# v1_1_0.net
KiCad netlist of a schematic drawn in EAGLE
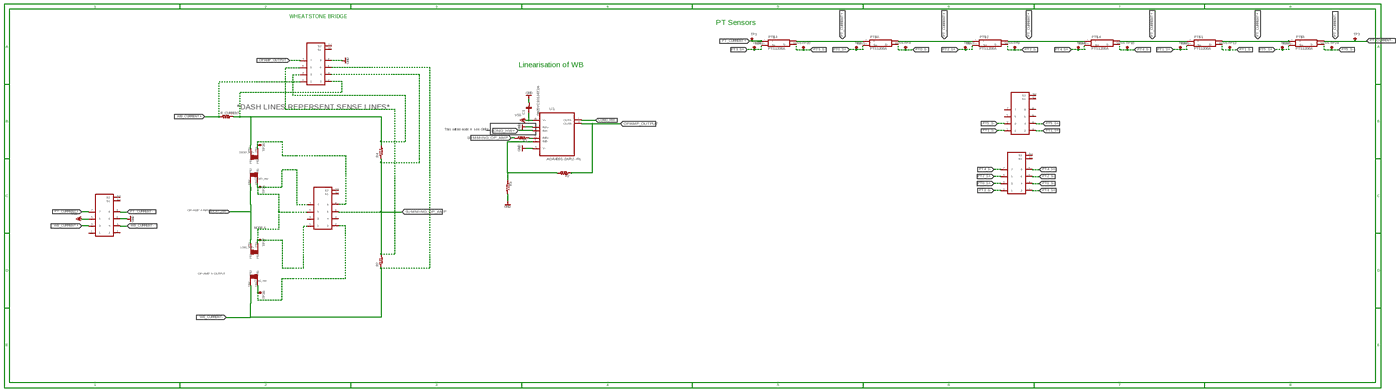
[diagram p0: schematic, sheet 1, overview]
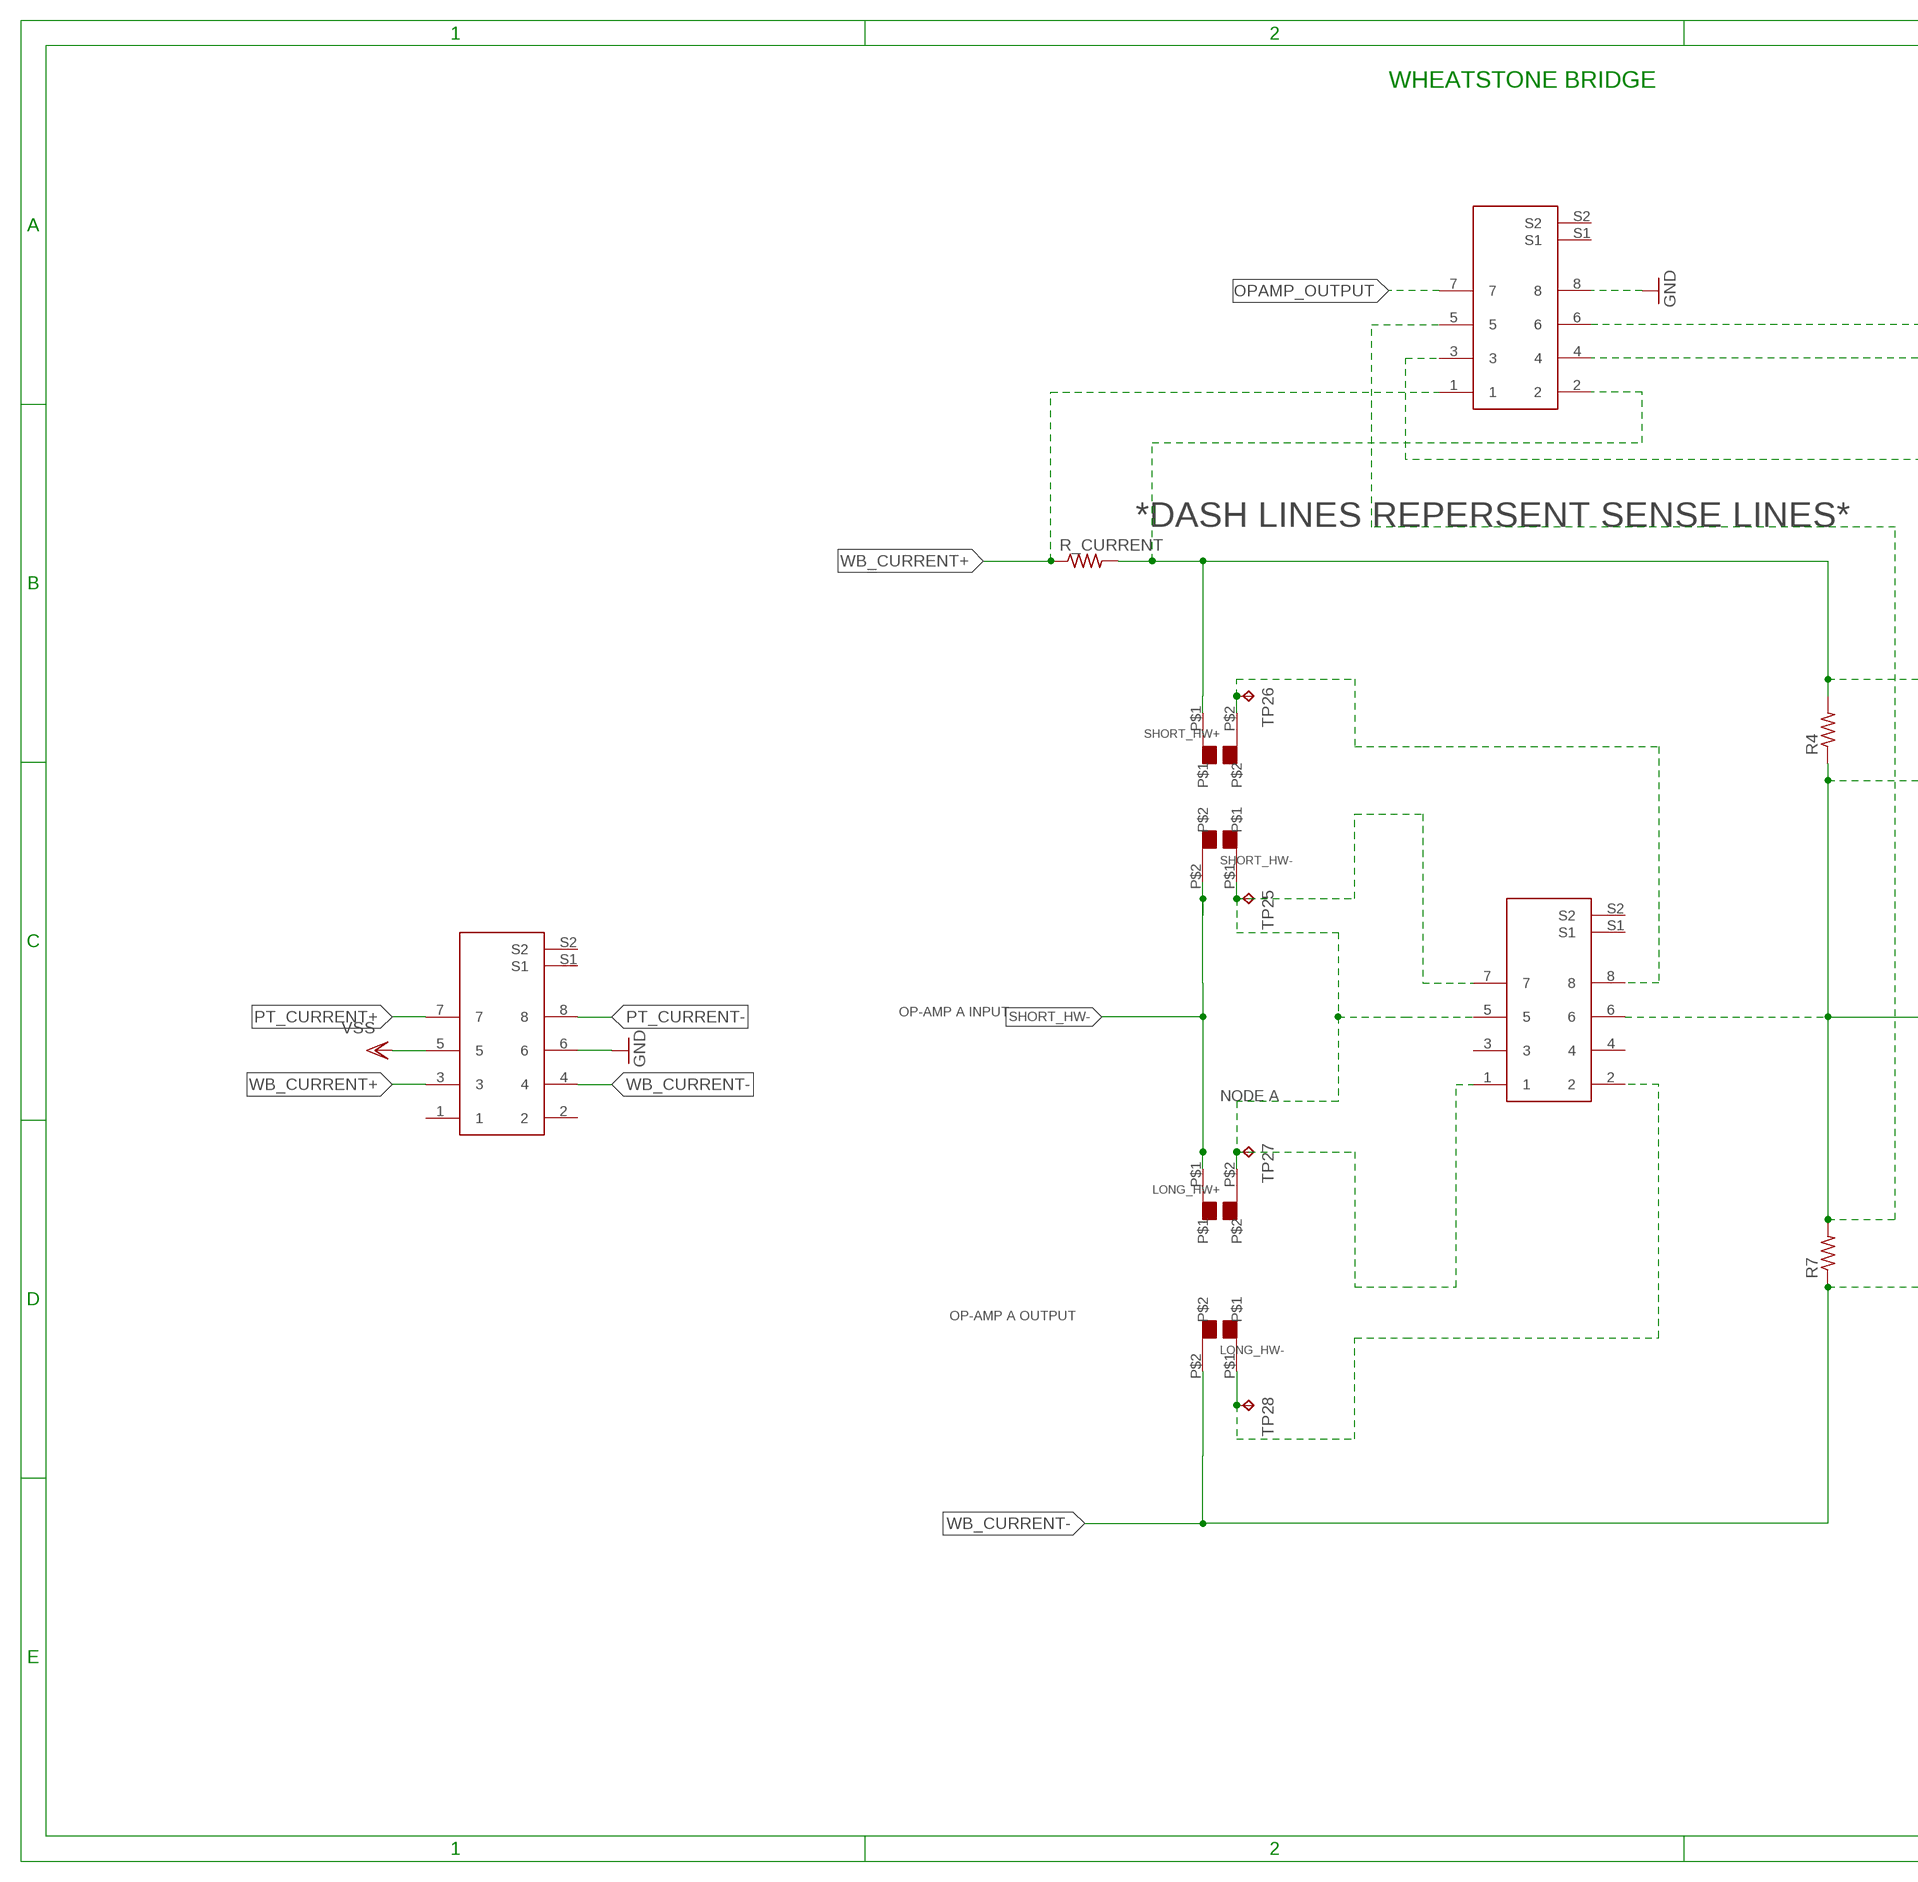
[diagram p1: schematic, sheet 1, part 1 of 4]
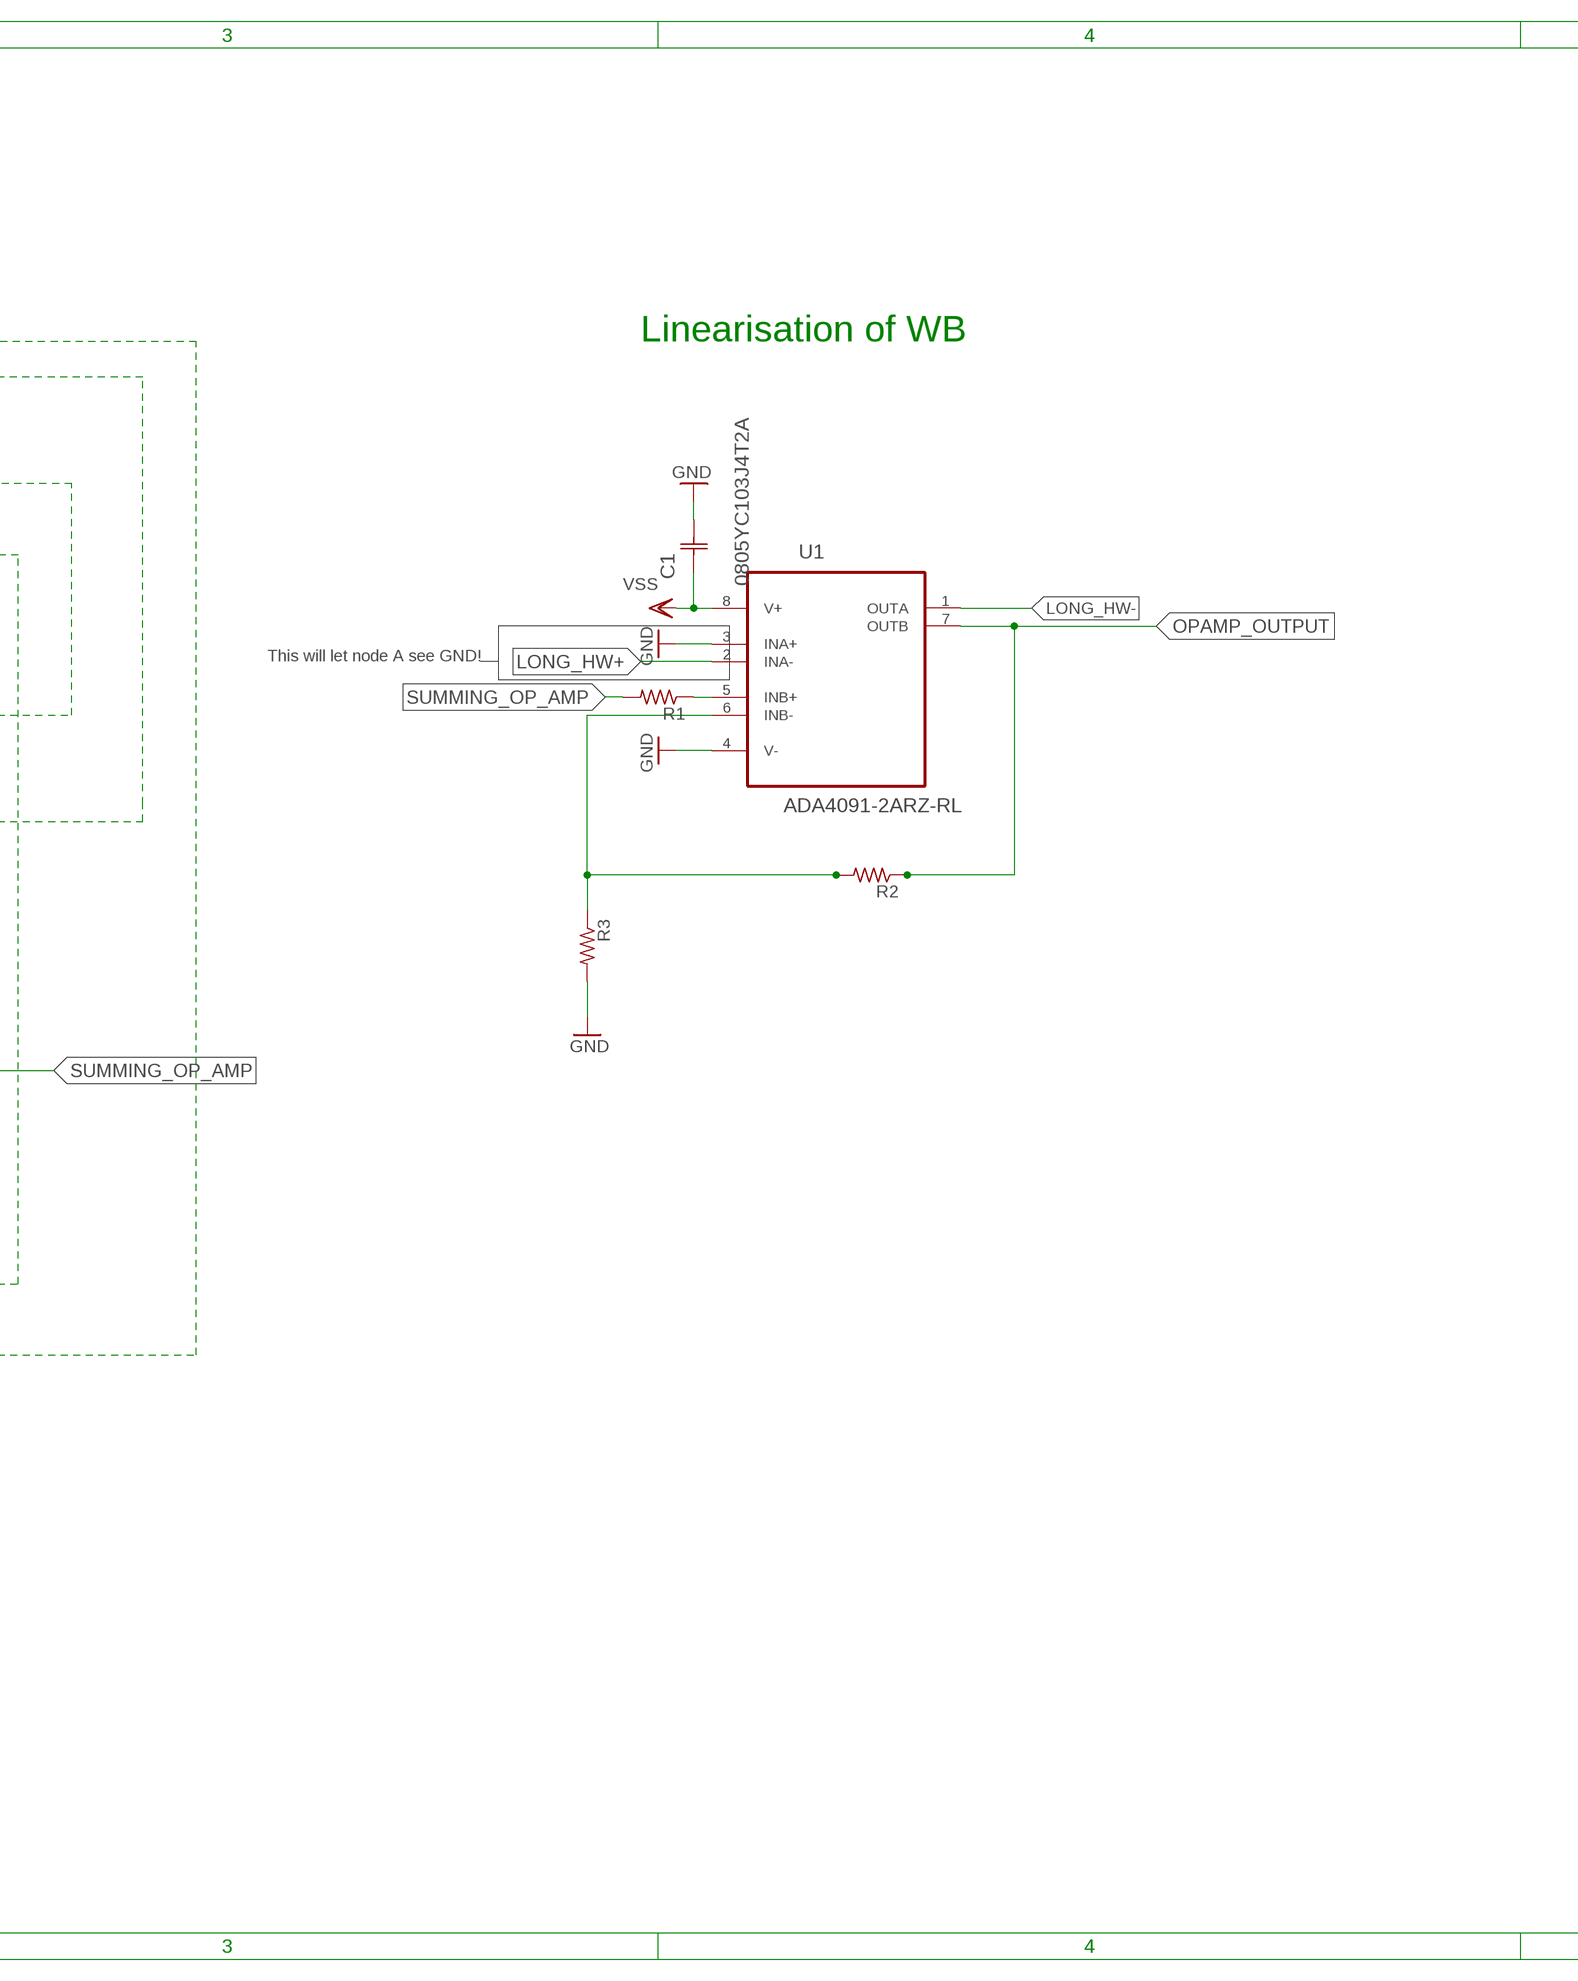
[diagram p2: schematic, sheet 1, part 2 of 4]
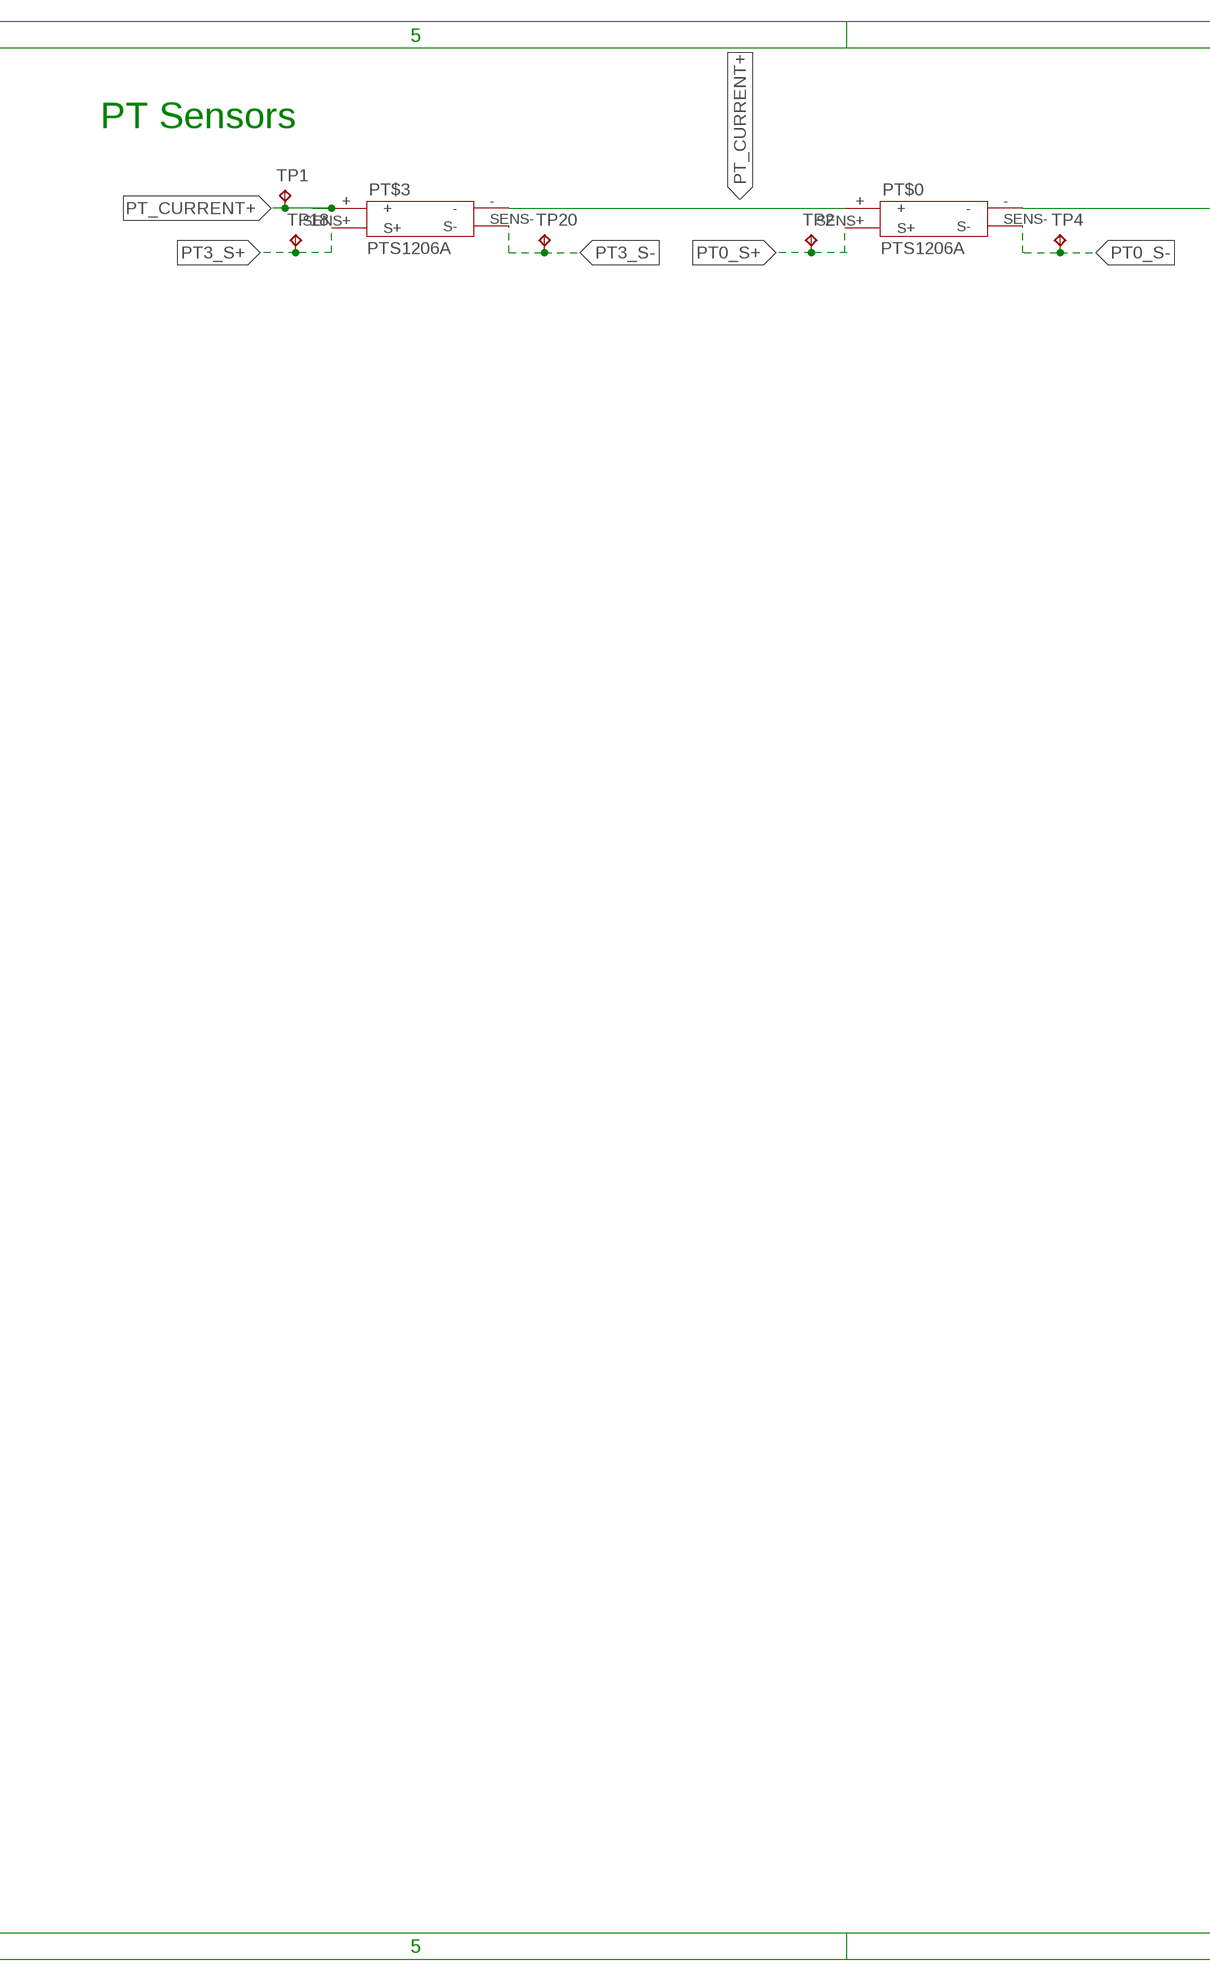
[diagram p3: schematic, sheet 1, part 3 of 4]
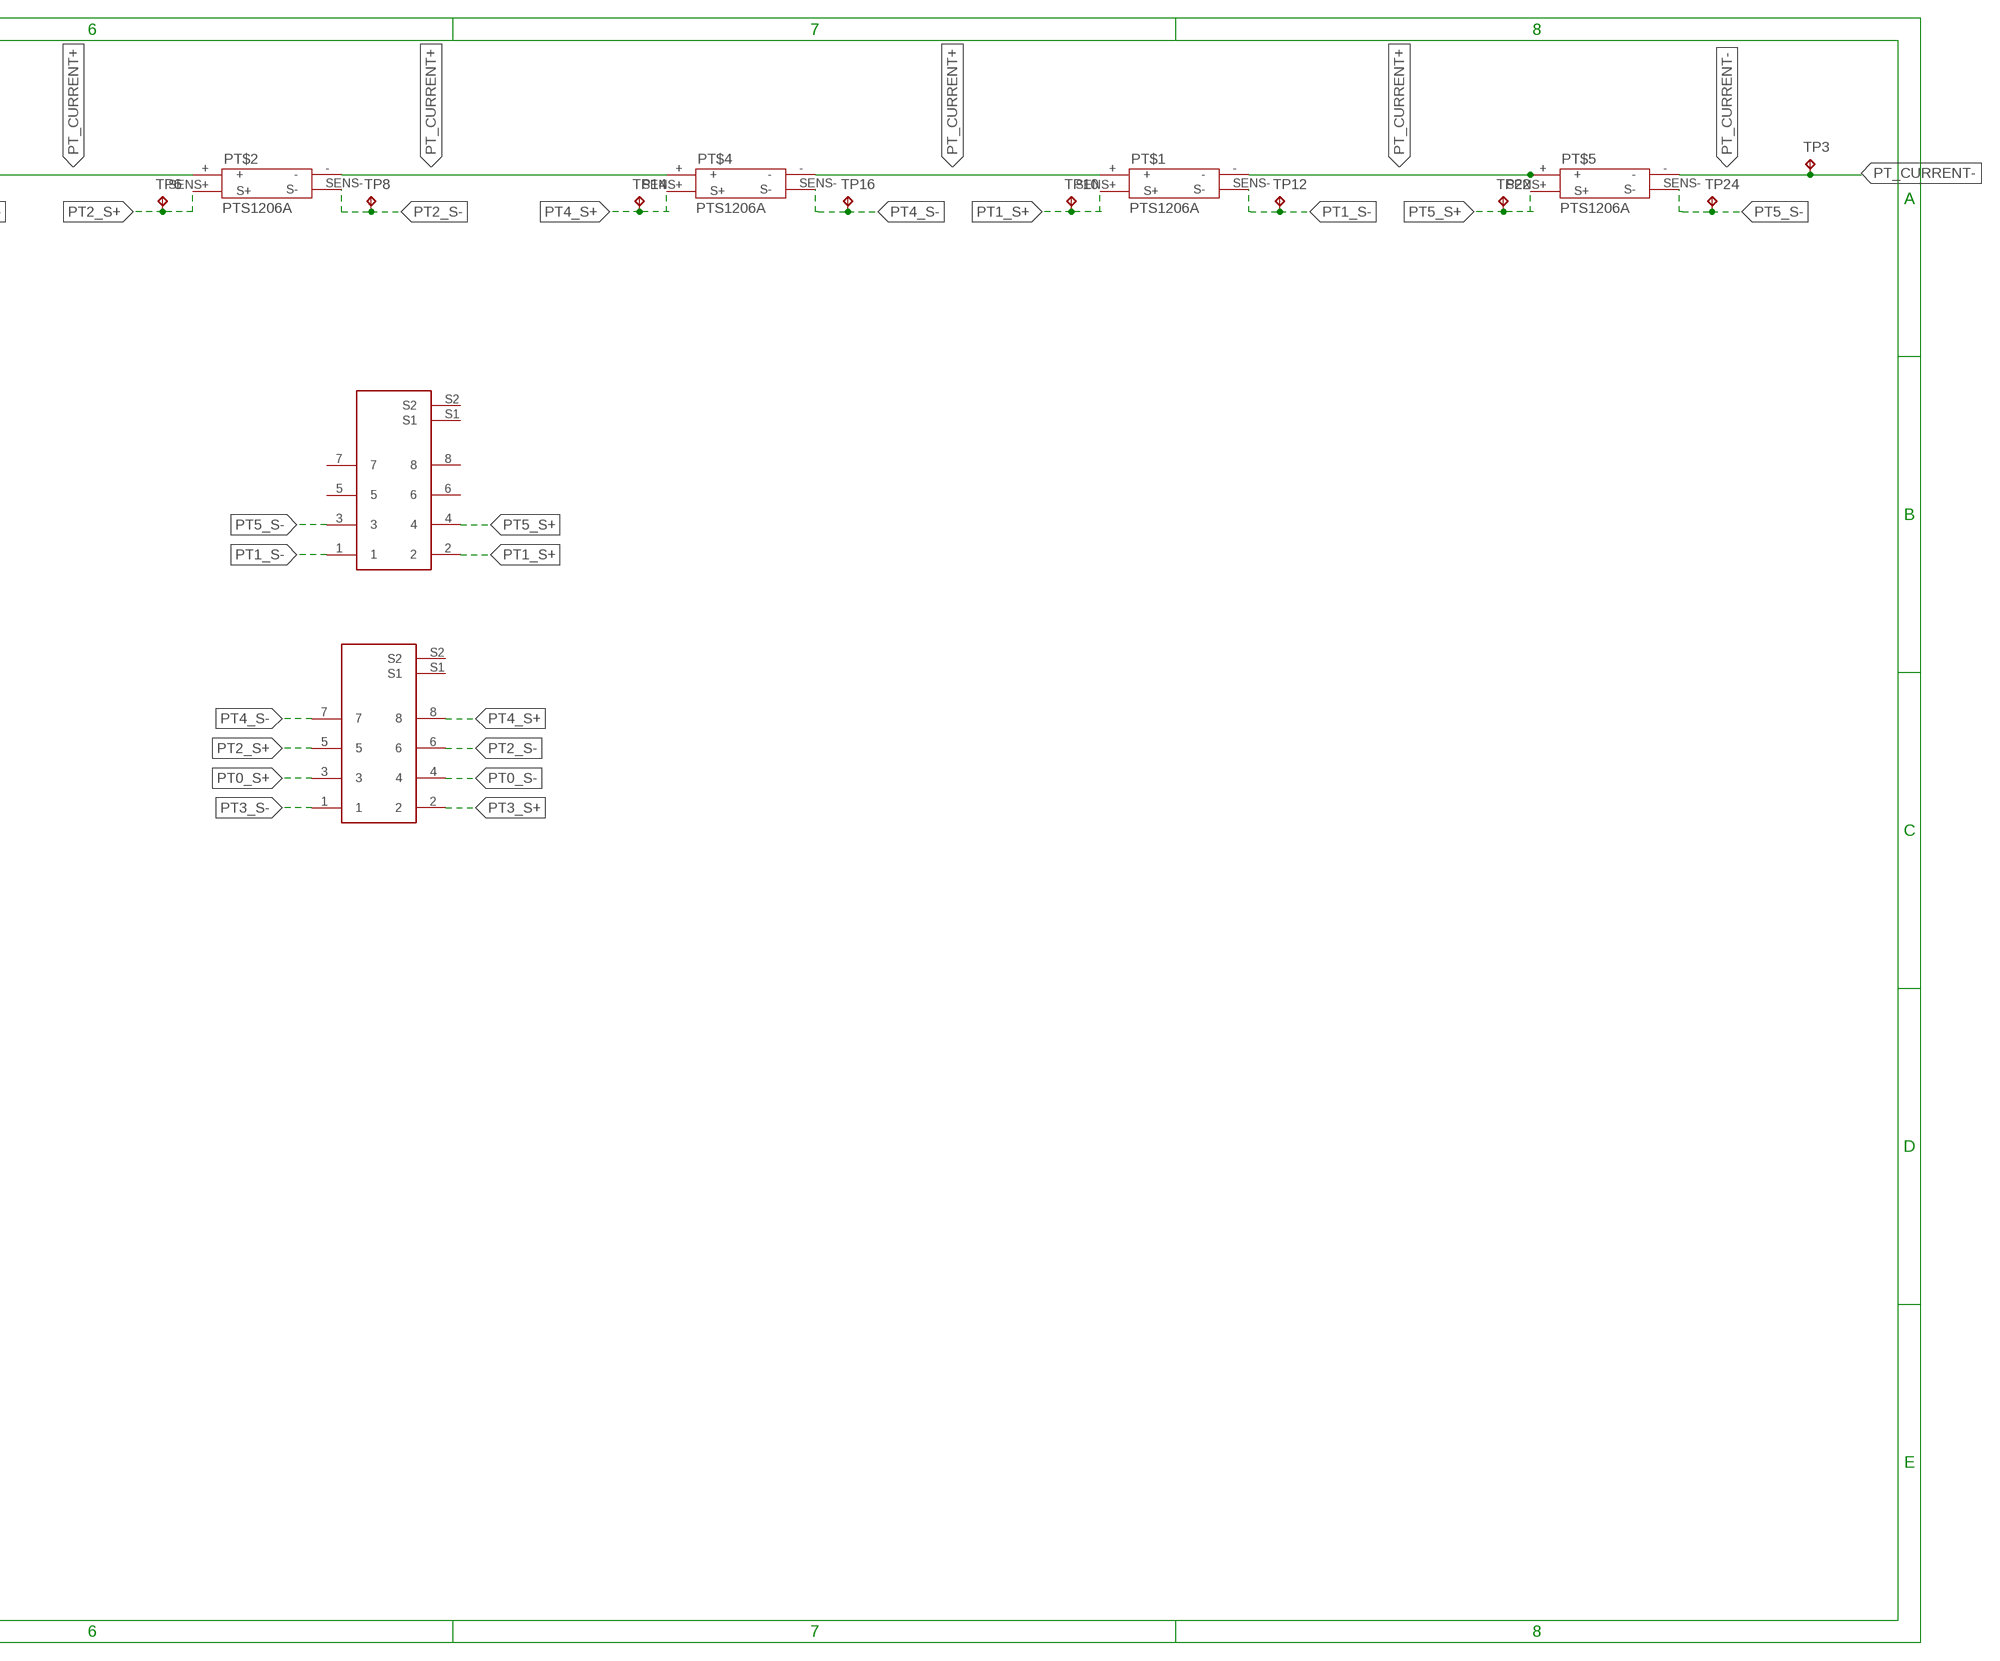
[diagram p4: schematic, sheet 1, part 4 of 4]

(export (version "E")
  (design (tool "Eeschema 10.0.6"))
  (components
    (comp (ref "C1")
      (value "0805YC103J4T2A")
      (footprint "eagle-import:CAPC2012X94N")
      (fields (field (name "MF") "AVX"))
      (libsource (lib "eagle-import") (part "0805YC103J4T2A"))
    )
    (comp (ref "LONG_HW+")
      (value "WIREPOINT_1A")
      (footprint "eagle-import:WIREPOINT")
      (libsource (lib "eagle-import") (part "WIREPOINT_1A"))
    )
    (comp (ref "LONG_HW-")
      (value "WIREPOINT_1A")
      (footprint "eagle-import:WIREPOINT")
      (libsource (lib "eagle-import") (part "WIREPOINT_1A"))
    )
    (comp (ref "POWER")
      (value "RJ45_CONNECTOR")
      (footprint "eagle-import:RJ45_CONNNECTOR")
      (libsource (lib "eagle-import") (part "RJ45_CONNECTOR"))
    )
    (comp (ref "PT$0")
      (value "PTS1206A")
      (footprint "eagle-import:CAPMP3216X166")
      (libsource (lib "eagle-import") (part "PTS1206A"))
    )
    (comp (ref "PT$1")
      (value "PTS1206A")
      (footprint "eagle-import:CAPMP3216X166")
      (libsource (lib "eagle-import") (part "PTS1206A"))
    )
    (comp (ref "PT$2")
      (value "PTS1206A")
      (footprint "eagle-import:CAPMP3216X166")
      (libsource (lib "eagle-import") (part "PTS1206A"))
    )
    (comp (ref "PT$3")
      (value "PTS1206A")
      (footprint "eagle-import:CAPMP3216X166")
      (libsource (lib "eagle-import") (part "PTS1206A"))
    )
    (comp (ref "PT$4")
      (value "PTS1206A")
      (footprint "eagle-import:CAPMP3216X166")
      (libsource (lib "eagle-import") (part "PTS1206A"))
    )
    (comp (ref "PT$5")
      (value "PTS1206A")
      (footprint "eagle-import:CAPMP3216X166")
      (libsource (lib "eagle-import") (part "PTS1206A"))
    )
    (comp (ref "PT_SENS1")
      (value "RJ45_CONNECTOR")
      (footprint "eagle-import:RJ45_CONNNECTOR")
      (libsource (lib "eagle-import") (part "RJ45_CONNECTOR"))
    )
    (comp (ref "PT_SENS2")
      (value "RJ45_CONNECTOR")
      (footprint "eagle-import:RJ45_CONNNECTOR")
      (libsource (lib "eagle-import") (part "RJ45_CONNECTOR"))
    )
    (comp (ref "R1")
      (value "R-US_M0805")
      (footprint "eagle-import:M0805")
      (libsource (lib "eagle-import") (part "R-US_M0805"))
    )
    (comp (ref "R2")
      (value "R-US_M0805")
      (footprint "eagle-import:M0805")
      (libsource (lib "eagle-import") (part "R-US_M0805"))
    )
    (comp (ref "R3")
      (value "R-US_M0805")
      (footprint "eagle-import:M0805")
      (libsource (lib "eagle-import") (part "R-US_M0805"))
    )
    (comp (ref "R4")
      (value "R-US_M0805")
      (footprint "eagle-import:M0805")
      (libsource (lib "eagle-import") (part "R-US_M0805"))
    )
    (comp (ref "R7")
      (value "R-US_M0805")
      (footprint "eagle-import:M0805")
      (libsource (lib "eagle-import") (part "R-US_M0805"))
    )
    (comp (ref "R_CURRENT")
      (value "R-US_M0805")
      (footprint "eagle-import:M0805")
      (libsource (lib "eagle-import") (part "R-US_M0805"))
    )
    (comp (ref "SHORT_HW+")
      (value "WIREPOINT_1A")
      (footprint "eagle-import:WIREPOINT")
      (libsource (lib "eagle-import") (part "WIREPOINT_1A"))
    )
    (comp (ref "SHORT_HW-")
      (value "WIREPOINT_1A")
      (footprint "eagle-import:WIREPOINT")
      (libsource (lib "eagle-import") (part "WIREPOINT_1A"))
    )
    (comp (ref "TP1")
      (value "TPTP10SQ")
      (footprint "eagle-import:TP10SQ")
      (libsource (lib "eagle-import") (part "TPTP10SQ"))
    )
    (comp (ref "TP2")
      (value "TPTP10SQ")
      (footprint "eagle-import:TP10SQ")
      (libsource (lib "eagle-import") (part "TPTP10SQ"))
    )
    (comp (ref "TP3")
      (value "TPTP10SQ")
      (footprint "eagle-import:TP10SQ")
      (libsource (lib "eagle-import") (part "TPTP10SQ"))
    )
    (comp (ref "TP4")
      (value "TPTP10SQ")
      (footprint "eagle-import:TP10SQ")
      (libsource (lib "eagle-import") (part "TPTP10SQ"))
    )
    (comp (ref "TP6")
      (value "TPTP10SQ")
      (footprint "eagle-import:TP10SQ")
      (libsource (lib "eagle-import") (part "TPTP10SQ"))
    )
    (comp (ref "TP8")
      (value "TPTP10SQ")
      (footprint "eagle-import:TP10SQ")
      (libsource (lib "eagle-import") (part "TPTP10SQ"))
    )
    (comp (ref "TP10")
      (value "TPTP10SQ")
      (footprint "eagle-import:TP10SQ")
      (libsource (lib "eagle-import") (part "TPTP10SQ"))
    )
    (comp (ref "TP12")
      (value "TPTP10SQ")
      (footprint "eagle-import:TP10SQ")
      (libsource (lib "eagle-import") (part "TPTP10SQ"))
    )
    (comp (ref "TP14")
      (value "TPTP10SQ")
      (footprint "eagle-import:TP10SQ")
      (libsource (lib "eagle-import") (part "TPTP10SQ"))
    )
    (comp (ref "TP16")
      (value "TPTP10SQ")
      (footprint "eagle-import:TP10SQ")
      (libsource (lib "eagle-import") (part "TPTP10SQ"))
    )
    (comp (ref "TP18")
      (value "TPTP10SQ")
      (footprint "eagle-import:TP10SQ")
      (libsource (lib "eagle-import") (part "TPTP10SQ"))
    )
    (comp (ref "TP20")
      (value "TPTP10SQ")
      (footprint "eagle-import:TP10SQ")
      (libsource (lib "eagle-import") (part "TPTP10SQ"))
    )
    (comp (ref "TP22")
      (value "TPTP10SQ")
      (footprint "eagle-import:TP10SQ")
      (libsource (lib "eagle-import") (part "TPTP10SQ"))
    )
    (comp (ref "TP24")
      (value "TPTP10SQ")
      (footprint "eagle-import:TP10SQ")
      (libsource (lib "eagle-import") (part "TPTP10SQ"))
    )
    (comp (ref "TP25")
      (value "TPTP10SQ")
      (footprint "eagle-import:TP10SQ")
      (libsource (lib "eagle-import") (part "TPTP10SQ"))
    )
    (comp (ref "TP26")
      (value "TPTP10SQ")
      (footprint "eagle-import:TP10SQ")
      (libsource (lib "eagle-import") (part "TPTP10SQ"))
    )
    (comp (ref "TP27")
      (value "TPTP10SQ")
      (footprint "eagle-import:TP10SQ")
      (libsource (lib "eagle-import") (part "TPTP10SQ"))
    )
    (comp (ref "TP28")
      (value "TPTP10SQ")
      (footprint "eagle-import:TP10SQ")
      (libsource (lib "eagle-import") (part "TPTP10SQ"))
    )
    (comp (ref "U1")
      (value "ADA4091-2ARZ-RL")
      (footprint "eagle-import:SOIC127P600X175-8N")
      (fields (field (name "MF") "Analog"))
      (libsource (lib "eagle-import") (part "ADA4091-2ARZ-RL"))
    )
    (comp (ref "WB_SENS1")
      (value "RJ45_CONNECTOR")
      (footprint "eagle-import:RJ45_CONNNECTOR")
      (libsource (lib "eagle-import") (part "RJ45_CONNECTOR"))
    )
    (comp (ref "WB_SENS2")
      (value "RJ45_CONNECTOR")
      (footprint "eagle-import:RJ45_CONNNECTOR")
      (libsource (lib "eagle-import") (part "RJ45_CONNECTOR"))
    )
  )
  (nets
    (net (code "1") (name "GND") (class "Default")
      (node (ref "C1") (pin "2") (pinfunction "C2_2") (pintype "passive"))
      (node (ref "POWER") (pin "6") (pinfunction "6_6") (pintype "bidirectional"))
      (node (ref "R3") (pin "2") (pinfunction "2_2") (pintype "passive"))
      (node (ref "U1") (pin "3") (pinfunction "INA+_3") (pintype "input"))
      (node (ref "U1") (pin "4") (pinfunction "V-_4") (pintype "power_in"))
      (node (ref "WB_SENS2") (pin "8") (pinfunction "8_8") (pintype "bidirectional"))
    )
    (net (code "2") (name "LONG_HW+") (class "Default")
      (node (ref "U1") (pin "2") (pinfunction "INA-_2") (pintype "input"))
    )
    (net (code "3") (name "LONG_HW-") (class "Default")
      (node (ref "U1") (pin "1") (pinfunction "OUTA_1") (pintype "output"))
    )
    (net (code "4") (name "Net-(LONG_HW+-PadP$2)") (class "Default")
      (node (ref "LONG_HW+") (pin "P$2") (pinfunction "P$2_P$2") (pintype "bidirectional"))
      (node (ref "SHORT_HW-") (pin "P$1") (pinfunction "P$1_P$1") (pintype "bidirectional"))
      (node (ref "TP25") (pin "TP") (pinfunction "TP_TP") (pintype "input"))
      (node (ref "TP27") (pin "TP") (pinfunction "TP_TP") (pintype "input"))
      (node (ref "WB_SENS1") (pin "1") (pinfunction "1_1") (pintype "bidirectional"))
      (node (ref "WB_SENS1") (pin "5") (pinfunction "5_5") (pintype "bidirectional"))
      (node (ref "WB_SENS1") (pin "7") (pinfunction "7_7") (pintype "bidirectional"))
    )
    (net (code "5") (name "Net-(LONG_HW--PadP$1)") (class "Default")
      (node (ref "LONG_HW-") (pin "P$1") (pinfunction "P$1_P$1") (pintype "bidirectional"))
      (node (ref "TP28") (pin "TP") (pinfunction "TP_TP") (pintype "input"))
      (node (ref "WB_SENS1") (pin "2") (pinfunction "2_2") (pintype "bidirectional"))
    )
    (net (code "6") (name "Net-(SHORT_HW+-PadP$2)") (class "Default")
      (node (ref "SHORT_HW+") (pin "P$2") (pinfunction "P$2_P$2") (pintype "bidirectional"))
      (node (ref "TP26") (pin "TP") (pinfunction "TP_TP") (pintype "input"))
      (node (ref "WB_SENS1") (pin "8") (pinfunction "8_8") (pintype "bidirectional"))
    )
    (net (code "7") (name "Net-(U1-INB+)") (class "Default")
      (node (ref "R1") (pin "1") (pinfunction "1_1") (pintype "passive"))
      (node (ref "U1") (pin "5") (pinfunction "INB+_5") (pintype "input"))
    )
    (net (code "8") (name "Net-(U1-INB-)") (class "Default")
      (node (ref "R2") (pin "2") (pinfunction "2_2") (pintype "passive"))
      (node (ref "R3") (pin "1") (pinfunction "1_1") (pintype "passive"))
      (node (ref "U1") (pin "6") (pinfunction "INB-_6") (pintype "input"))
    )
    (net (code "9") (name "OPAMP_OUTPUT") (class "Default")
      (node (ref "R2") (pin "1") (pinfunction "1_1") (pintype "passive"))
      (node (ref "U1") (pin "7") (pinfunction "OUTB_7") (pintype "output"))
      (node (ref "WB_SENS2") (pin "7") (pinfunction "7_7") (pintype "bidirectional"))
    )
    (net (code "10") (name "PT0_S+") (class "Default")
      (node (ref "PT$0") (pin "SENS+") (pinfunction "S+_SENS+") (pintype "bidirectional"))
      (node (ref "PT_SENS2") (pin "3") (pinfunction "3_3") (pintype "bidirectional"))
      (node (ref "TP2") (pin "TP") (pinfunction "TP_TP") (pintype "input"))
    )
    (net (code "11") (name "PT0_S-") (class "Default")
      (node (ref "PT$0") (pin "SENS-") (pinfunction "S-_SENS-") (pintype "bidirectional"))
      (node (ref "PT_SENS2") (pin "4") (pinfunction "4_4") (pintype "bidirectional"))
      (node (ref "TP4") (pin "TP") (pinfunction "TP_TP") (pintype "input"))
    )
    (net (code "12") (name "PT1_S+") (class "Default")
      (node (ref "PT$1") (pin "SENS+") (pinfunction "S+_SENS+") (pintype "bidirectional"))
      (node (ref "PT_SENS1") (pin "2") (pinfunction "2_2") (pintype "bidirectional"))
      (node (ref "TP10") (pin "TP") (pinfunction "TP_TP") (pintype "input"))
    )
    (net (code "13") (name "PT1_S-") (class "Default")
      (node (ref "PT$1") (pin "SENS-") (pinfunction "S-_SENS-") (pintype "bidirectional"))
      (node (ref "PT_SENS1") (pin "1") (pinfunction "1_1") (pintype "bidirectional"))
      (node (ref "TP12") (pin "TP") (pinfunction "TP_TP") (pintype "input"))
    )
    (net (code "14") (name "PT2_S+") (class "Default")
      (node (ref "PT$2") (pin "SENS+") (pinfunction "S+_SENS+") (pintype "bidirectional"))
      (node (ref "PT_SENS2") (pin "5") (pinfunction "5_5") (pintype "bidirectional"))
      (node (ref "TP6") (pin "TP") (pinfunction "TP_TP") (pintype "input"))
    )
    (net (code "15") (name "PT2_S-") (class "Default")
      (node (ref "PT$2") (pin "SENS-") (pinfunction "S-_SENS-") (pintype "bidirectional"))
      (node (ref "PT_SENS2") (pin "6") (pinfunction "6_6") (pintype "bidirectional"))
      (node (ref "TP8") (pin "TP") (pinfunction "TP_TP") (pintype "input"))
    )
    (net (code "16") (name "PT3_S+") (class "Default")
      (node (ref "PT$3") (pin "SENS+") (pinfunction "S+_SENS+") (pintype "bidirectional"))
      (node (ref "PT_SENS2") (pin "2") (pinfunction "2_2") (pintype "bidirectional"))
      (node (ref "TP18") (pin "TP") (pinfunction "TP_TP") (pintype "input"))
    )
    (net (code "17") (name "PT3_S-") (class "Default")
      (node (ref "PT$3") (pin "SENS-") (pinfunction "S-_SENS-") (pintype "bidirectional"))
      (node (ref "PT_SENS2") (pin "1") (pinfunction "1_1") (pintype "bidirectional"))
      (node (ref "TP20") (pin "TP") (pinfunction "TP_TP") (pintype "input"))
    )
    (net (code "18") (name "PT4_S+") (class "Default")
      (node (ref "PT$4") (pin "SENS+") (pinfunction "S+_SENS+") (pintype "bidirectional"))
      (node (ref "PT_SENS2") (pin "8") (pinfunction "8_8") (pintype "bidirectional"))
      (node (ref "TP14") (pin "TP") (pinfunction "TP_TP") (pintype "input"))
    )
    (net (code "19") (name "PT4_S-") (class "Default")
      (node (ref "PT$4") (pin "SENS-") (pinfunction "S-_SENS-") (pintype "bidirectional"))
      (node (ref "PT_SENS2") (pin "7") (pinfunction "7_7") (pintype "bidirectional"))
      (node (ref "TP16") (pin "TP") (pinfunction "TP_TP") (pintype "input"))
    )
    (net (code "20") (name "PT5_S+") (class "Default")
      (node (ref "PT$5") (pin "SENS+") (pinfunction "S+_SENS+") (pintype "bidirectional"))
      (node (ref "PT_SENS1") (pin "4") (pinfunction "4_4") (pintype "bidirectional"))
      (node (ref "TP22") (pin "TP") (pinfunction "TP_TP") (pintype "input"))
    )
    (net (code "21") (name "PT5_S-") (class "Default")
      (node (ref "PT$5") (pin "SENS-") (pinfunction "S-_SENS-") (pintype "bidirectional"))
      (node (ref "PT_SENS1") (pin "3") (pinfunction "3_3") (pintype "bidirectional"))
      (node (ref "TP24") (pin "TP") (pinfunction "TP_TP") (pintype "input"))
    )
    (net (code "22") (name "PT_CURRENT+") (class "Default")
      (node (ref "POWER") (pin "7") (pinfunction "7_7") (pintype "bidirectional"))
      (node (ref "PT$0") (pin "+") (pinfunction "+_+") (pintype "bidirectional"))
      (node (ref "PT$0") (pin "-") (pinfunction "-_-") (pintype "bidirectional"))
      (node (ref "PT$1") (pin "+") (pinfunction "+_+") (pintype "bidirectional"))
      (node (ref "PT$1") (pin "-") (pinfunction "-_-") (pintype "bidirectional"))
      (node (ref "PT$2") (pin "+") (pinfunction "+_+") (pintype "bidirectional"))
      (node (ref "PT$2") (pin "-") (pinfunction "-_-") (pintype "bidirectional"))
      (node (ref "PT$3") (pin "+") (pinfunction "+_+") (pintype "bidirectional"))
      (node (ref "PT$3") (pin "-") (pinfunction "-_-") (pintype "bidirectional"))
      (node (ref "PT$4") (pin "+") (pinfunction "+_+") (pintype "bidirectional"))
      (node (ref "PT$4") (pin "-") (pinfunction "-_-") (pintype "bidirectional"))
      (node (ref "PT$5") (pin "+") (pinfunction "+_+") (pintype "bidirectional"))
      (node (ref "TP1") (pin "TP") (pinfunction "TP_TP") (pintype "input"))
    )
    (net (code "23") (name "PT_CURRENT-") (class "Default")
      (node (ref "POWER") (pin "8") (pinfunction "8_8") (pintype "bidirectional"))
      (node (ref "PT$5") (pin "-") (pinfunction "-_-") (pintype "bidirectional"))
      (node (ref "TP3") (pin "TP") (pinfunction "TP_TP") (pintype "input"))
    )
    (net (code "24") (name "SHORT_HW+") (class "Default")
      (node (ref "R4") (pin "2") (pinfunction "2_2") (pintype "passive"))
      (node (ref "R_CURRENT") (pin "2") (pinfunction "2_2") (pintype "passive"))
      (node (ref "SHORT_HW+") (pin "P$1") (pinfunction "P$1_P$1") (pintype "bidirectional"))
      (node (ref "WB_SENS2") (pin "2") (pinfunction "2_2") (pintype "bidirectional"))
      (node (ref "WB_SENS2") (pin "3") (pinfunction "3_3") (pintype "bidirectional"))
    )
    (net (code "25") (name "SHORT_HW-") (class "Default")
      (node (ref "LONG_HW+") (pin "P$1") (pinfunction "P$1_P$1") (pintype "bidirectional"))
      (node (ref "SHORT_HW-") (pin "P$2") (pinfunction "P$2_P$2") (pintype "bidirectional"))
    )
    (net (code "26") (name "SUMMING_OP_AMP") (class "Default")
      (node (ref "R1") (pin "2") (pinfunction "2_2") (pintype "passive"))
      (node (ref "R4") (pin "1") (pinfunction "1_1") (pintype "passive"))
      (node (ref "R7") (pin "2") (pinfunction "2_2") (pintype "passive"))
      (node (ref "WB_SENS1") (pin "6") (pinfunction "6_6") (pintype "bidirectional"))
      (node (ref "WB_SENS2") (pin "4") (pinfunction "4_4") (pintype "bidirectional"))
      (node (ref "WB_SENS2") (pin "5") (pinfunction "5_5") (pintype "bidirectional"))
    )
    (net (code "27") (name "VSS") (class "Default")
      (node (ref "C1") (pin "1") (pinfunction "C1_1") (pintype "passive"))
      (node (ref "POWER") (pin "5") (pinfunction "5_5") (pintype "bidirectional"))
      (node (ref "U1") (pin "8") (pinfunction "V+_8") (pintype "power_in"))
    )
    (net (code "28") (name "WB_CURRENT+") (class "Default")
      (node (ref "POWER") (pin "3") (pinfunction "3_3") (pintype "bidirectional"))
      (node (ref "R_CURRENT") (pin "1") (pinfunction "1_1") (pintype "passive"))
      (node (ref "WB_SENS2") (pin "1") (pinfunction "1_1") (pintype "bidirectional"))
    )
    (net (code "29") (name "WB_CURRENT-") (class "Default")
      (node (ref "LONG_HW-") (pin "P$2") (pinfunction "P$2_P$2") (pintype "bidirectional"))
      (node (ref "POWER") (pin "4") (pinfunction "4_4") (pintype "bidirectional"))
      (node (ref "R7") (pin "1") (pinfunction "1_1") (pintype "passive"))
      (node (ref "WB_SENS2") (pin "6") (pinfunction "6_6") (pintype "bidirectional"))
    )
    (net (code "30") (name "unconnected-(POWER-Pad1)") (class "Default")
      (node (ref "POWER") (pin "1") (pinfunction "1_1") (pintype "bidirectional"))
    )
    (net (code "31") (name "unconnected-(POWER-Pad2)") (class "Default")
      (node (ref "POWER") (pin "2") (pinfunction "2_2") (pintype "bidirectional"))
    )
    (net (code "32") (name "unconnected-(POWER-PadS1)") (class "Default")
      (node (ref "POWER") (pin "S1") (pinfunction "S1_S1") (pintype "bidirectional"))
    )
    (net (code "33") (name "unconnected-(POWER-PadS2)") (class "Default")
      (node (ref "POWER") (pin "S2") (pinfunction "S2_S2") (pintype "bidirectional"))
    )
    (net (code "34") (name "unconnected-(PT_SENS1-Pad5)") (class "Default")
      (node (ref "PT_SENS1") (pin "5") (pinfunction "5_5") (pintype "bidirectional"))
    )
    (net (code "35") (name "unconnected-(PT_SENS1-Pad6)") (class "Default")
      (node (ref "PT_SENS1") (pin "6") (pinfunction "6_6") (pintype "bidirectional"))
    )
    (net (code "36") (name "unconnected-(PT_SENS1-Pad7)") (class "Default")
      (node (ref "PT_SENS1") (pin "7") (pinfunction "7_7") (pintype "bidirectional"))
    )
    (net (code "37") (name "unconnected-(PT_SENS1-Pad8)") (class "Default")
      (node (ref "PT_SENS1") (pin "8") (pinfunction "8_8") (pintype "bidirectional"))
    )
    (net (code "38") (name "unconnected-(PT_SENS1-PadS1)") (class "Default")
      (node (ref "PT_SENS1") (pin "S1") (pinfunction "S1_S1") (pintype "bidirectional"))
    )
    (net (code "39") (name "unconnected-(PT_SENS1-PadS2)") (class "Default")
      (node (ref "PT_SENS1") (pin "S2") (pinfunction "S2_S2") (pintype "bidirectional"))
    )
    (net (code "40") (name "unconnected-(PT_SENS2-PadS1)") (class "Default")
      (node (ref "PT_SENS2") (pin "S1") (pinfunction "S1_S1") (pintype "bidirectional"))
    )
    (net (code "41") (name "unconnected-(PT_SENS2-PadS2)") (class "Default")
      (node (ref "PT_SENS2") (pin "S2") (pinfunction "S2_S2") (pintype "bidirectional"))
    )
    (net (code "42") (name "unconnected-(WB_SENS1-Pad3)") (class "Default")
      (node (ref "WB_SENS1") (pin "3") (pinfunction "3_3") (pintype "bidirectional"))
    )
    (net (code "43") (name "unconnected-(WB_SENS1-Pad4)") (class "Default")
      (node (ref "WB_SENS1") (pin "4") (pinfunction "4_4") (pintype "bidirectional"))
    )
    (net (code "44") (name "unconnected-(WB_SENS1-PadS1)") (class "Default")
      (node (ref "WB_SENS1") (pin "S1") (pinfunction "S1_S1") (pintype "bidirectional"))
    )
    (net (code "45") (name "unconnected-(WB_SENS1-PadS2)") (class "Default")
      (node (ref "WB_SENS1") (pin "S2") (pinfunction "S2_S2") (pintype "bidirectional"))
    )
    (net (code "46") (name "unconnected-(WB_SENS2-PadS1)") (class "Default")
      (node (ref "WB_SENS2") (pin "S1") (pinfunction "S1_S1") (pintype "bidirectional"))
    )
    (net (code "47") (name "unconnected-(WB_SENS2-PadS2)") (class "Default")
      (node (ref "WB_SENS2") (pin "S2") (pinfunction "S2_S2") (pintype "bidirectional"))
    )
  )
)
